# mrf89_v1_1.net
KiCad netlist of a schematic drawn in EAGLE
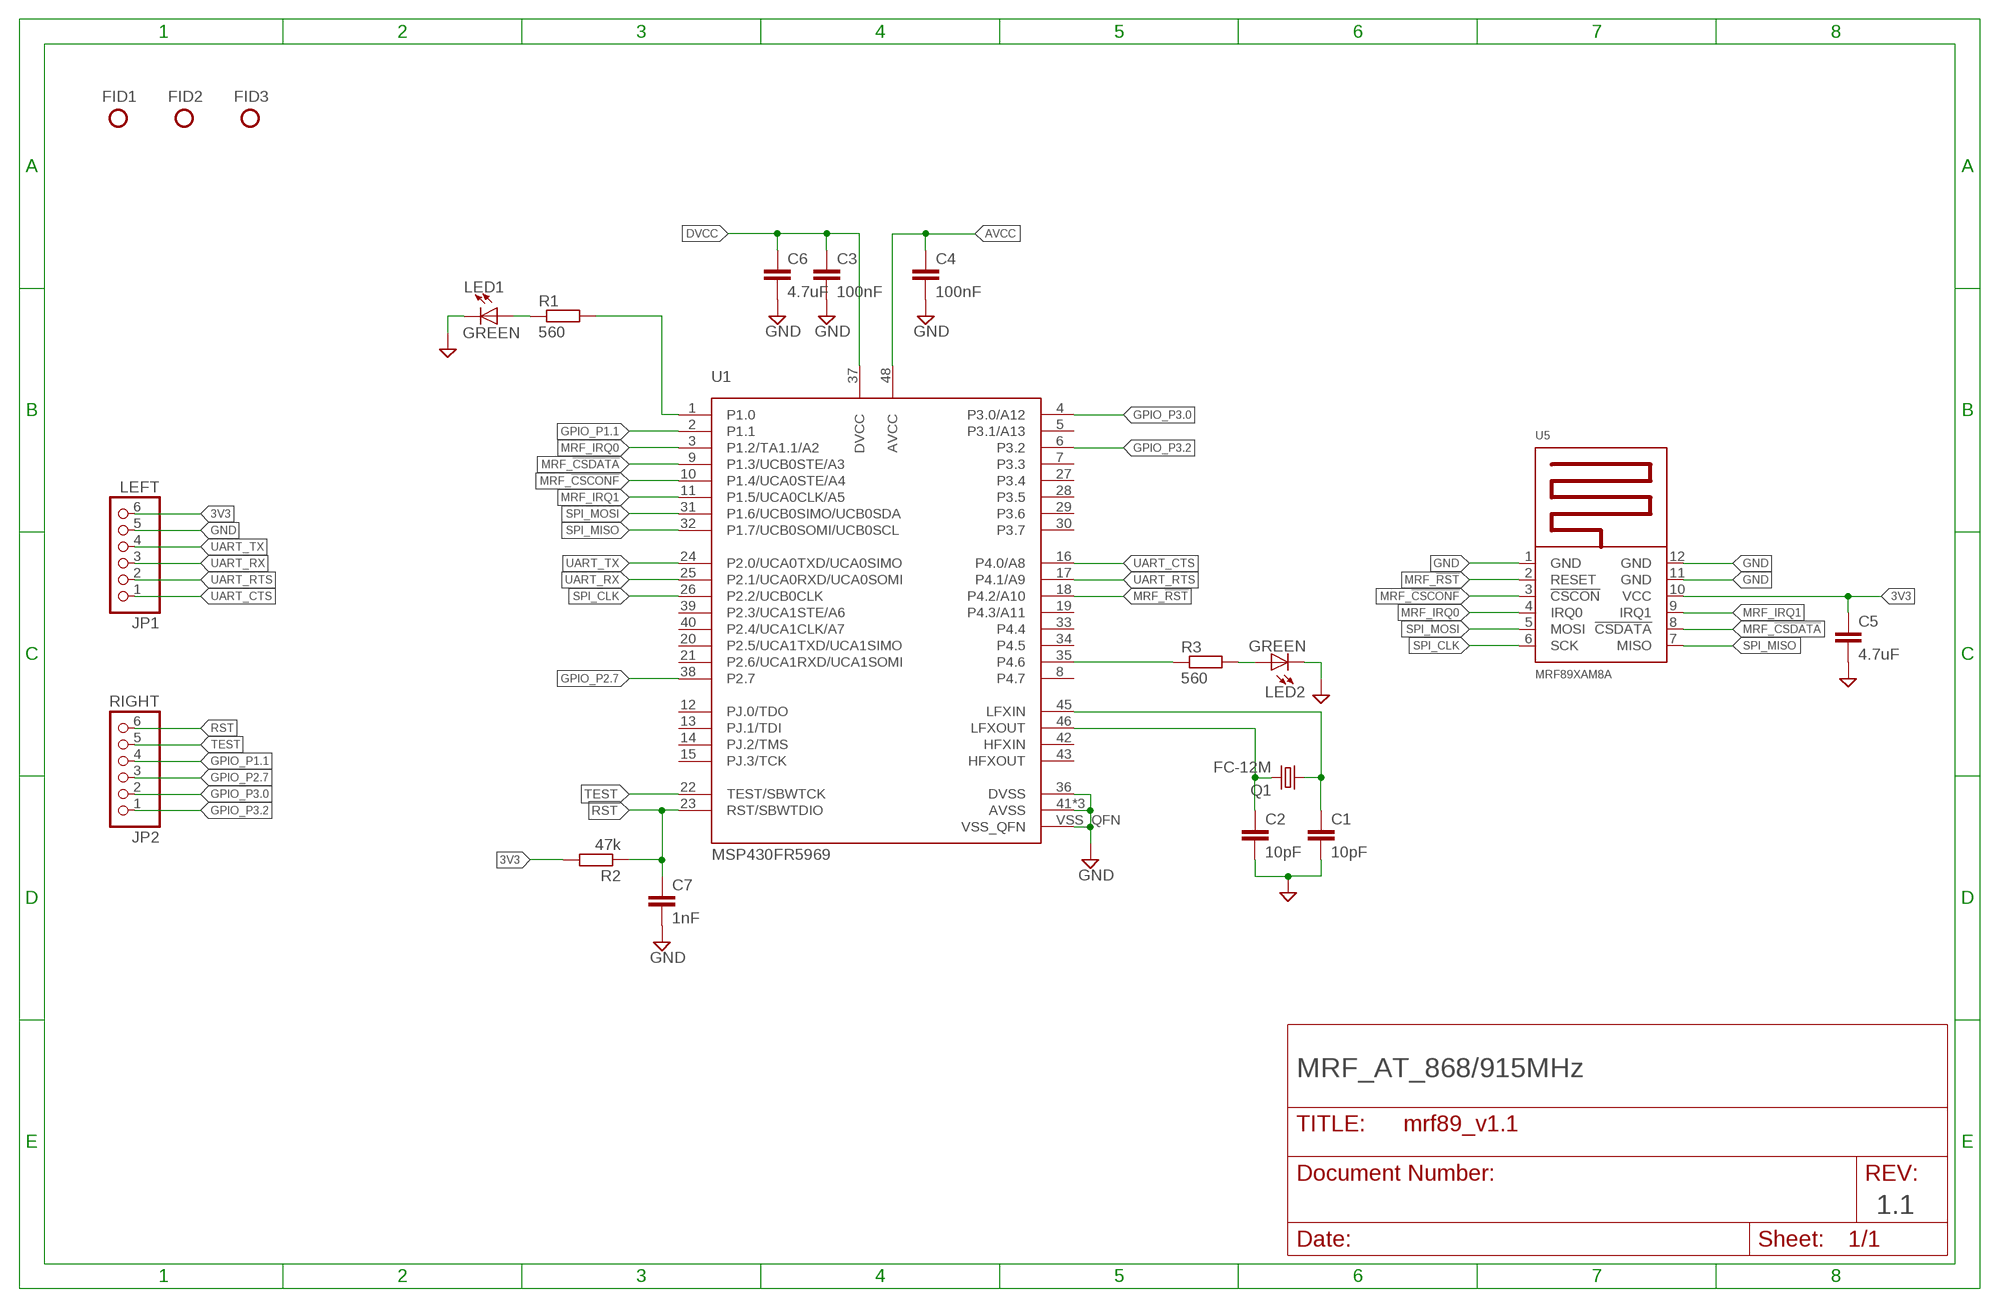
[diagram p0: schematic, sheet 1]

(export (version "E")
  (design (tool "Eeschema 10.0.6"))
  (components
    (comp (ref "C1")
      (value "10pF")
      (footprint "eagle-import:C0603")
      (libsource (lib "eagle-import") (part "C-EUC0603"))
    )
    (comp (ref "C2")
      (value "10pF")
      (footprint "eagle-import:C0603")
      (libsource (lib "eagle-import") (part "C-EUC0603"))
    )
    (comp (ref "C3")
      (value "100nF")
      (footprint "eagle-import:C0603")
      (libsource (lib "eagle-import") (part "C-EUC0603"))
    )
    (comp (ref "C4")
      (value "100nF")
      (footprint "eagle-import:C0603")
      (libsource (lib "eagle-import") (part "C-EUC0603"))
    )
    (comp (ref "C5")
      (value "4.7uF")
      (footprint "eagle-import:C0603")
      (libsource (lib "eagle-import") (part "C-EUC0603"))
    )
    (comp (ref "C6")
      (value "4.7uF")
      (footprint "eagle-import:C0603")
      (libsource (lib "eagle-import") (part "C-EUC0603"))
    )
    (comp (ref "C7")
      (value "1nF")
      (footprint "eagle-import:C0603")
      (libsource (lib "eagle-import") (part "C-EUC0603"))
    )
    (comp (ref "FID1")
      (value "FIDUCIAL")
      (footprint "eagle-import:FIDUCIAL")
      (libsource (lib "eagle-import") (part "FIDUCIAL"))
    )
    (comp (ref "FID2")
      (value "FIDUCIAL")
      (footprint "eagle-import:FIDUCIAL")
      (libsource (lib "eagle-import") (part "FIDUCIAL"))
    )
    (comp (ref "FID3")
      (value "FIDUCIAL")
      (footprint "eagle-import:FIDUCIAL")
      (libsource (lib "eagle-import") (part "FIDUCIAL"))
    )
    (comp (ref "JP1")
      (value "LEFT")
      (footprint "eagle-import:1X06")
      (libsource (lib "eagle-import") (part "PINHD-1X6"))
    )
    (comp (ref "JP2")
      (value "RIGHT")
      (footprint "eagle-import:1X06")
      (libsource (lib "eagle-import") (part "PINHD-1X6"))
    )
    (comp (ref "LED1")
      (value "GREEN")
      (footprint "eagle-import:CHIP-LED0603")
      (libsource (lib "eagle-import") (part "LEDCHIP-LED0603"))
    )
    (comp (ref "LED2")
      (value "GREEN")
      (footprint "eagle-import:CHIP-LED0603")
      (libsource (lib "eagle-import") (part "LEDCHIP-LED0603"))
    )
    (comp (ref "Q1")
      (value "FC-12M")
      (footprint "eagle-import:FC-12M")
      (libsource (lib "eagle-import") (part "FC-12M"))
    )
    (comp (ref "R1")
      (value "560")
      (footprint "eagle-import:R0603")
      (libsource (lib "eagle-import") (part "R-EU_R0603"))
    )
    (comp (ref "R2")
      (value "47k")
      (footprint "eagle-import:R0603")
      (libsource (lib "eagle-import") (part "R-EU_R0603"))
    )
    (comp (ref "R3")
      (value "560")
      (footprint "eagle-import:R0603")
      (libsource (lib "eagle-import") (part "R-EU_R0603"))
    )
    (comp (ref "U1")
      (value "MSP430FR5969")
      (footprint "eagle-import:S-PVQFN-N48")
      (libsource (lib "eagle-import") (part "MSP430FR5969"))
    )
    (comp (ref "U5")
      (value "MRF89XAM8A")
      (footprint "eagle-import:MRF89XAMXA")
      (libsource (lib "eagle-import") (part "MRF89XAM8A"))
    )
  )
  (nets
    (net (code "1") (name "/MRF_~{CSCONF}") (class "Default")
      (node (ref "U1") (pin "10") (pinfunction "P1.4/UCA0STE/A4_10") (pintype "bidirectional"))
      (node (ref "U5") (pin "3") (pinfunction "~{CSCON}_3") (pintype "input"))
    )
    (net (code "2") (name "/MRF_~{CSDATA}") (class "Default")
      (node (ref "U1") (pin "9") (pinfunction "P1.3/UCB0STE/A3_9") (pintype "bidirectional"))
      (node (ref "U5") (pin "8") (pinfunction "~{CSDATA}_8") (pintype "input"))
    )
    (net (code "3") (name "/MRF_~{RST}") (class "Default")
      (node (ref "U1") (pin "18") (pinfunction "P4.2/A10_18") (pintype "bidirectional"))
      (node (ref "U5") (pin "2") (pinfunction "RESET_2") (pintype "input"))
    )
    (net (code "4") (name "3V3") (class "Default")
      (node (ref "C5") (pin "1") (pinfunction "1_1") (pintype "passive"))
      (node (ref "JP1") (pin "6") (pinfunction "6_6") (pintype "passive"))
      (node (ref "R2") (pin "2") (pinfunction "2_2") (pintype "passive"))
      (node (ref "U5") (pin "10") (pinfunction "VCC_10") (pintype "power_in"))
    )
    (net (code "5") (name "AVCC") (class "Default")
      (node (ref "C4") (pin "1") (pinfunction "1_1") (pintype "passive"))
      (node (ref "U1") (pin "48") (pinfunction "AVCC_48") (pintype "power_in"))
    )
    (net (code "6") (name "DVCC") (class "Default")
      (node (ref "C3") (pin "1") (pinfunction "1_1") (pintype "passive"))
      (node (ref "C6") (pin "1") (pinfunction "1_1") (pintype "passive"))
      (node (ref "U1") (pin "37") (pinfunction "DVCC_37") (pintype "power_in"))
    )
    (net (code "7") (name "GND") (class "Default")
      (node (ref "C1") (pin "2") (pinfunction "2_2") (pintype "passive"))
      (node (ref "C2") (pin "2") (pinfunction "2_2") (pintype "passive"))
      (node (ref "C3") (pin "2") (pinfunction "2_2") (pintype "passive"))
      (node (ref "C4") (pin "2") (pinfunction "2_2") (pintype "passive"))
      (node (ref "C5") (pin "2") (pinfunction "2_2") (pintype "passive"))
      (node (ref "C6") (pin "2") (pinfunction "2_2") (pintype "passive"))
      (node (ref "C7") (pin "2") (pinfunction "2_2") (pintype "passive"))
      (node (ref "JP1") (pin "5") (pinfunction "5_5") (pintype "passive"))
      (node (ref "LED1") (pin "C") (pinfunction "C_C") (pintype "passive"))
      (node (ref "LED2") (pin "C") (pinfunction "C_C") (pintype "passive"))
      (node (ref "U1") (pin "36") (pinfunction "DVSS_36") (pintype "power_in"))
      (node (ref "U1") (pin "41") (pinfunction "AVSS_41") (pintype "power_in"))
      (node (ref "U1") (pin "44") (pinfunction "AVSS_44") (pintype "power_in"))
      (node (ref "U1") (pin "47") (pinfunction "AVSS_47") (pintype "power_in"))
      (node (ref "U1") (pin "VSS_QFN") (pinfunction "VSS_QFN_VSS_QFN") (pintype "bidirectional"))
      (node (ref "U5") (pin "1") (pinfunction "GND_1") (pintype "power_in"))
      (node (ref "U5") (pin "11") (pinfunction "GND_11") (pintype "power_in"))
      (node (ref "U5") (pin "12") (pinfunction "GND_12") (pintype "power_in"))
    )
    (net (code "8") (name "GPIO_P1.1") (class "Default")
      (node (ref "JP2") (pin "4") (pinfunction "4_4") (pintype "passive"))
      (node (ref "U1") (pin "2") (pinfunction "P1.1_2") (pintype "bidirectional"))
    )
    (net (code "9") (name "GPIO_P2.7") (class "Default")
      (node (ref "JP2") (pin "3") (pinfunction "3_3") (pintype "passive"))
      (node (ref "U1") (pin "38") (pinfunction "P2.7_38") (pintype "bidirectional"))
    )
    (net (code "10") (name "GPIO_P3.0") (class "Default")
      (node (ref "JP2") (pin "2") (pinfunction "2_2") (pintype "passive"))
      (node (ref "U1") (pin "4") (pinfunction "P3.0/A12_4") (pintype "bidirectional"))
    )
    (net (code "11") (name "GPIO_P3.2") (class "Default")
      (node (ref "JP2") (pin "1") (pinfunction "1_1") (pintype "passive"))
      (node (ref "U1") (pin "6") (pinfunction "P3.2_6") (pintype "bidirectional"))
    )
    (net (code "12") (name "MRF_IRQ0") (class "Default")
      (node (ref "U1") (pin "3") (pinfunction "P1.2/TA1.1/A2_3") (pintype "bidirectional"))
      (node (ref "U5") (pin "4") (pinfunction "IRQ0_4") (pintype "output"))
    )
    (net (code "13") (name "MRF_IRQ1") (class "Default")
      (node (ref "U1") (pin "11") (pinfunction "P1.5/UCA0CLK/A5_11") (pintype "bidirectional"))
      (node (ref "U5") (pin "9") (pinfunction "IRQ1_9") (pintype "output"))
    )
    (net (code "14") (name "Net-(LED1-PadA)") (class "Default")
      (node (ref "LED1") (pin "A") (pinfunction "A_A") (pintype "passive"))
      (node (ref "R1") (pin "1") (pinfunction "1_1") (pintype "passive"))
    )
    (net (code "15") (name "Net-(LED2-PadA)") (class "Default")
      (node (ref "LED2") (pin "A") (pinfunction "A_A") (pintype "passive"))
      (node (ref "R3") (pin "2") (pinfunction "2_2") (pintype "passive"))
    )
    (net (code "16") (name "Net-(U1-LFXIN)") (class "Default")
      (node (ref "C1") (pin "1") (pinfunction "1_1") (pintype "passive"))
      (node (ref "Q1") (pin "1") (pinfunction "1_1") (pintype "passive"))
      (node (ref "U1") (pin "45") (pinfunction "LFXIN_45") (pintype "bidirectional"))
    )
    (net (code "17") (name "Net-(U1-LFXOUT)") (class "Default")
      (node (ref "C2") (pin "1") (pinfunction "1_1") (pintype "passive"))
      (node (ref "Q1") (pin "2") (pinfunction "2_2") (pintype "passive"))
      (node (ref "U1") (pin "46") (pinfunction "LFXOUT_46") (pintype "bidirectional"))
    )
    (net (code "18") (name "Net-(U1-P1.0)") (class "Default")
      (node (ref "R1") (pin "2") (pinfunction "2_2") (pintype "passive"))
      (node (ref "U1") (pin "1") (pinfunction "P1.0_1") (pintype "bidirectional"))
    )
    (net (code "19") (name "Net-(U1-P4.6)") (class "Default")
      (node (ref "R3") (pin "1") (pinfunction "1_1") (pintype "passive"))
      (node (ref "U1") (pin "35") (pinfunction "P4.6_35") (pintype "bidirectional"))
    )
    (net (code "20") (name "RST") (class "Default")
      (node (ref "C7") (pin "1") (pinfunction "1_1") (pintype "passive"))
      (node (ref "JP2") (pin "6") (pinfunction "6_6") (pintype "passive"))
      (node (ref "R2") (pin "1") (pinfunction "1_1") (pintype "passive"))
      (node (ref "U1") (pin "23") (pinfunction "RST/SBWTDIO_23") (pintype "bidirectional"))
    )
    (net (code "21") (name "SPI_CLK") (class "Default")
      (node (ref "U1") (pin "26") (pinfunction "P2.2/UCB0CLK_26") (pintype "bidirectional"))
      (node (ref "U5") (pin "6") (pinfunction "SCK_6") (pintype "input"))
    )
    (net (code "22") (name "SPI_MISO") (class "Default")
      (node (ref "U1") (pin "32") (pinfunction "P1.7/UCB0SOMI/UCB0SCL_32") (pintype "bidirectional"))
      (node (ref "U5") (pin "7") (pinfunction "MISO_7") (pintype "output"))
    )
    (net (code "23") (name "SPI_MOSI") (class "Default")
      (node (ref "U1") (pin "31") (pinfunction "P1.6/UCB0SIMO/UCB0SDA_31") (pintype "bidirectional"))
      (node (ref "U5") (pin "5") (pinfunction "MOSI_5") (pintype "input"))
    )
    (net (code "24") (name "TEST") (class "Default")
      (node (ref "JP2") (pin "5") (pinfunction "5_5") (pintype "passive"))
      (node (ref "U1") (pin "22") (pinfunction "TEST/SBWTCK_22") (pintype "bidirectional"))
    )
    (net (code "25") (name "UART_CTS") (class "Default")
      (node (ref "JP1") (pin "1") (pinfunction "1_1") (pintype "passive"))
      (node (ref "U1") (pin "16") (pinfunction "P4.0/A8_16") (pintype "bidirectional"))
    )
    (net (code "26") (name "UART_RTS") (class "Default")
      (node (ref "JP1") (pin "2") (pinfunction "2_2") (pintype "passive"))
      (node (ref "U1") (pin "17") (pinfunction "P4.1/A9_17") (pintype "bidirectional"))
    )
    (net (code "27") (name "UART_RX") (class "Default")
      (node (ref "JP1") (pin "3") (pinfunction "3_3") (pintype "passive"))
      (node (ref "U1") (pin "25") (pinfunction "P2.1/UCA0RXD/UCA0SOMI_25") (pintype "bidirectional"))
    )
    (net (code "28") (name "UART_TX") (class "Default")
      (node (ref "JP1") (pin "4") (pinfunction "4_4") (pintype "passive"))
      (node (ref "U1") (pin "24") (pinfunction "P2.0/UCA0TXD/UCA0SIMO_24") (pintype "bidirectional"))
    )
    (net (code "29") (name "unconnected-(U1-HFXIN-Pad42)") (class "Default")
      (node (ref "U1") (pin "42") (pinfunction "HFXIN_42") (pintype "bidirectional"))
    )
    (net (code "30") (name "unconnected-(U1-HFXOUT-Pad43)") (class "Default")
      (node (ref "U1") (pin "43") (pinfunction "HFXOUT_43") (pintype "bidirectional"))
    )
    (net (code "31") (name "unconnected-(U1-P2.3{slash}UCA1STE{slash}A6-Pad39)") (class "Default")
      (node (ref "U1") (pin "39") (pinfunction "P2.3/UCA1STE/A6_39") (pintype "bidirectional"))
    )
    (net (code "32") (name "unconnected-(U1-P2.4{slash}UCA1CLK{slash}A7-Pad40)") (class "Default")
      (node (ref "U1") (pin "40") (pinfunction "P2.4/UCA1CLK/A7_40") (pintype "bidirectional"))
    )
    (net (code "33") (name "unconnected-(U1-P2.5{slash}UCA1TXD{slash}UCA1SIMO-Pad20)") (class "Default")
      (node (ref "U1") (pin "20") (pinfunction "P2.5/UCA1TXD/UCA1SIMO_20") (pintype "bidirectional"))
    )
    (net (code "34") (name "unconnected-(U1-P2.6{slash}UCA1RXD{slash}UCA1SOMI-Pad21)") (class "Default")
      (node (ref "U1") (pin "21") (pinfunction "P2.6/UCA1RXD/UCA1SOMI_21") (pintype "bidirectional"))
    )
    (net (code "35") (name "unconnected-(U1-P3.1{slash}A13-Pad5)") (class "Default")
      (node (ref "U1") (pin "5") (pinfunction "P3.1/A13_5") (pintype "bidirectional"))
    )
    (net (code "36") (name "unconnected-(U1-P3.3-Pad7)") (class "Default")
      (node (ref "U1") (pin "7") (pinfunction "P3.3_7") (pintype "bidirectional"))
    )
    (net (code "37") (name "unconnected-(U1-P3.4-Pad27)") (class "Default")
      (node (ref "U1") (pin "27") (pinfunction "P3.4_27") (pintype "bidirectional"))
    )
    (net (code "38") (name "unconnected-(U1-P3.5-Pad28)") (class "Default")
      (node (ref "U1") (pin "28") (pinfunction "P3.5_28") (pintype "bidirectional"))
    )
    (net (code "39") (name "unconnected-(U1-P3.6-Pad29)") (class "Default")
      (node (ref "U1") (pin "29") (pinfunction "P3.6_29") (pintype "bidirectional"))
    )
    (net (code "40") (name "unconnected-(U1-P3.7-Pad30)") (class "Default")
      (node (ref "U1") (pin "30") (pinfunction "P3.7_30") (pintype "bidirectional"))
    )
    (net (code "41") (name "unconnected-(U1-P4.3{slash}A11-Pad19)") (class "Default")
      (node (ref "U1") (pin "19") (pinfunction "P4.3/A11_19") (pintype "bidirectional"))
    )
    (net (code "42") (name "unconnected-(U1-P4.4-Pad33)") (class "Default")
      (node (ref "U1") (pin "33") (pinfunction "P4.4_33") (pintype "bidirectional"))
    )
    (net (code "43") (name "unconnected-(U1-P4.5-Pad34)") (class "Default")
      (node (ref "U1") (pin "34") (pinfunction "P4.5_34") (pintype "bidirectional"))
    )
    (net (code "44") (name "unconnected-(U1-P4.7-Pad8)") (class "Default")
      (node (ref "U1") (pin "8") (pinfunction "P4.7_8") (pintype "bidirectional"))
    )
    (net (code "45") (name "unconnected-(U1-PJ.0{slash}TDO-Pad12)") (class "Default")
      (node (ref "U1") (pin "12") (pinfunction "PJ.0/TDO_12") (pintype "bidirectional"))
    )
    (net (code "46") (name "unconnected-(U1-PJ.1{slash}TDI-Pad13)") (class "Default")
      (node (ref "U1") (pin "13") (pinfunction "PJ.1/TDI_13") (pintype "bidirectional"))
    )
    (net (code "47") (name "unconnected-(U1-PJ.2{slash}TMS-Pad14)") (class "Default")
      (node (ref "U1") (pin "14") (pinfunction "PJ.2/TMS_14") (pintype "bidirectional"))
    )
    (net (code "48") (name "unconnected-(U1-PJ.3{slash}TCK-Pad15)") (class "Default")
      (node (ref "U1") (pin "15") (pinfunction "PJ.3/TCK_15") (pintype "bidirectional"))
    )
  )
)
